# Boost_Kit.net
KiCad netlist of a schematic drawn in EAGLE
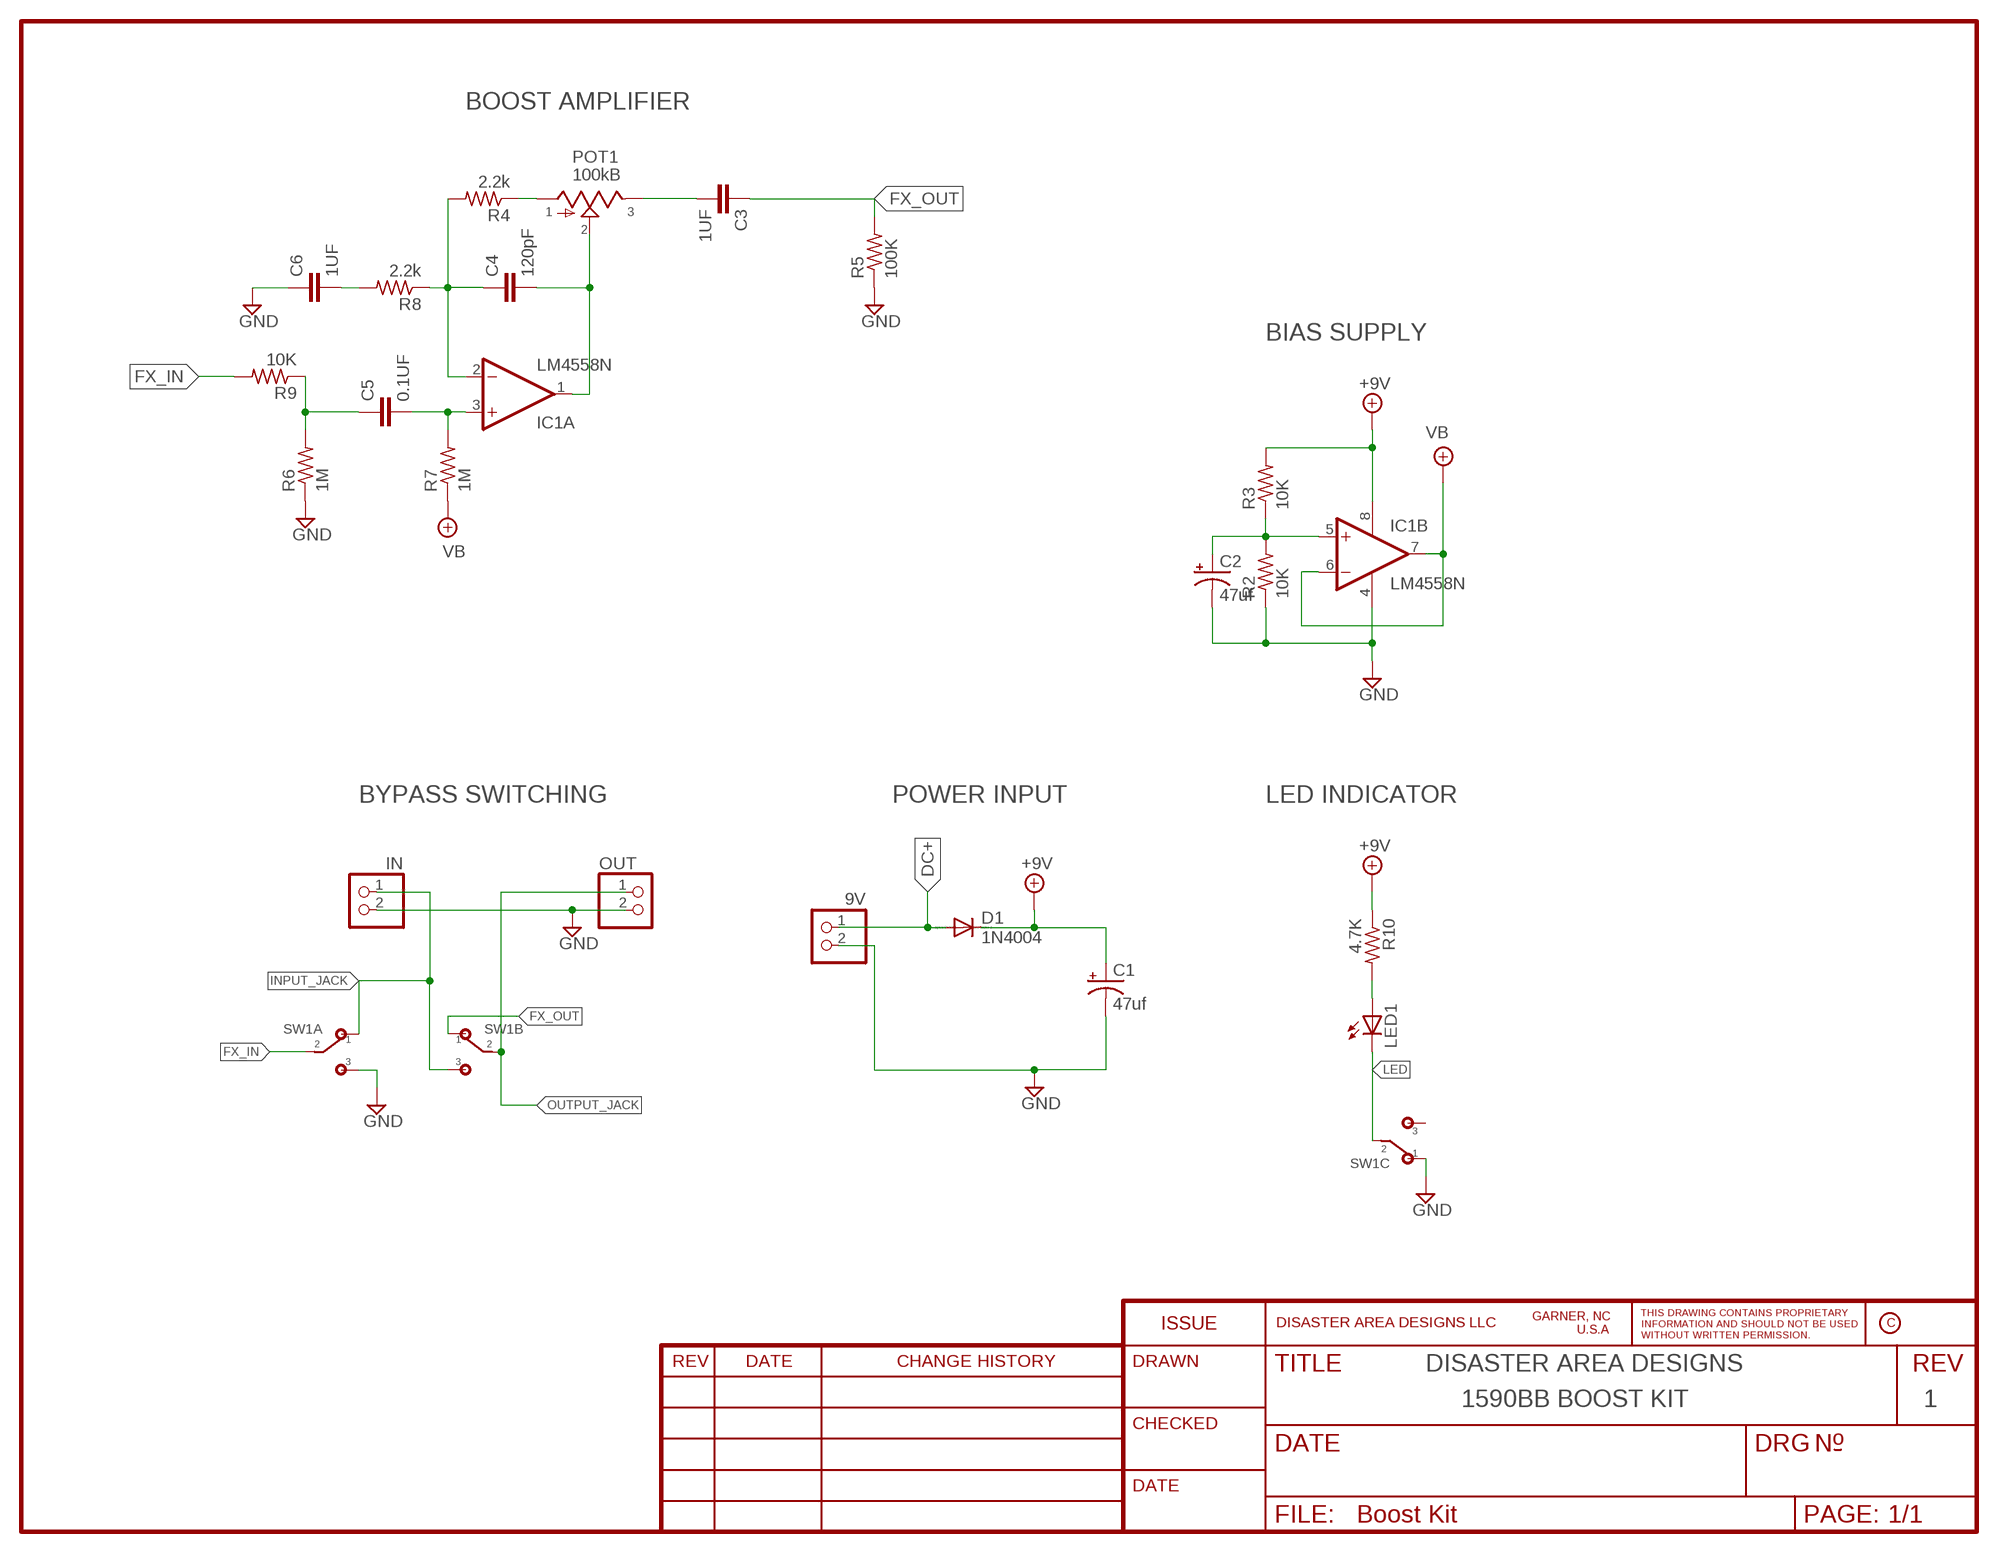
[diagram p0: schematic, sheet 1]

(export (version "E")
  (design (tool "Eeschema 10.0.6"))
  (components
    (comp (ref "9V")
      (value "PINHD-1X2")
      (footprint "eagle-import:1X02")
      (libsource (lib "eagle-import") (part "PINHD-1X2"))
    )
    (comp (ref "C1")
      (value "47uf")
      (footprint "eagle-import:E2,5-6")
      (libsource (lib "eagle-import") (part "CPOL-USE2.5-6"))
    )
    (comp (ref "C2")
      (value "47uf")
      (footprint "eagle-import:E2,5-6")
      (libsource (lib "eagle-import") (part "CPOL-USE2.5-6"))
    )
    (comp (ref "C3")
      (value "1UF")
      (footprint "eagle-import:072X035")
      (libsource (lib "eagle-import") (part "072X0352"))
    )
    (comp (ref "C4")
      (value "120pF")
      (footprint "eagle-import:072X035")
      (libsource (lib "eagle-import") (part "072X0352"))
    )
    (comp (ref "C5")
      (value "0.1UF")
      (footprint "eagle-import:072X035")
      (libsource (lib "eagle-import") (part "072X0352"))
    )
    (comp (ref "C6")
      (value "1UF")
      (footprint "eagle-import:072X035")
      (libsource (lib "eagle-import") (part "072X0352"))
    )
    (comp (ref "D1")
      (value "1N4004")
      (footprint "eagle-import:DO41-10")
      (libsource (lib "eagle-import") (part "1N4004"))
    )
    (comp (ref "IC1")
      (value "LM4558N")
      (footprint "eagle-import:DIL08")
      (libsource (lib "eagle-import") (part "4558NLM"))
    )
    (comp (ref "IN")
      (value "PINHD-1X2")
      (footprint "eagle-import:1X02")
      (libsource (lib "eagle-import") (part "PINHD-1X2"))
    )
    (comp (ref "LED1")
      (value "LED5MM")
      (footprint "eagle-import:LED5MM")
      (libsource (lib "eagle-import") (part "LED5MM"))
    )
    (comp (ref "OUT")
      (value "PINHD-1X2")
      (footprint "eagle-import:1X02")
      (libsource (lib "eagle-import") (part "PINHD-1X2"))
    )
    (comp (ref "POT1")
      (value "100kB")
      (footprint "eagle-import:16MM")
      (libsource (lib "eagle-import") (part "POT16MM"))
    )
    (comp (ref "R2")
      (value "10K")
      (footprint "eagle-import:R0207_4")
      (libsource (lib "eagle-import") (part "6MM.4"))
    )
    (comp (ref "R3")
      (value "10K")
      (footprint "eagle-import:R0207_4")
      (libsource (lib "eagle-import") (part "6MM.4"))
    )
    (comp (ref "R4")
      (value "2.2k")
      (footprint "eagle-import:R0207_4")
      (libsource (lib "eagle-import") (part "6MM.4"))
    )
    (comp (ref "R5")
      (value "100K")
      (footprint "eagle-import:R0207_4")
      (libsource (lib "eagle-import") (part "6MM.4"))
    )
    (comp (ref "R6")
      (value "1M")
      (footprint "eagle-import:R0207_4")
      (libsource (lib "eagle-import") (part "6MM.4"))
    )
    (comp (ref "R7")
      (value "1M")
      (footprint "eagle-import:R0207_4")
      (libsource (lib "eagle-import") (part "6MM.4"))
    )
    (comp (ref "R8")
      (value "2.2k")
      (footprint "eagle-import:R0207_4")
      (libsource (lib "eagle-import") (part "6MM.4"))
    )
    (comp (ref "R9")
      (value "10K")
      (footprint "eagle-import:R0207_4")
      (libsource (lib "eagle-import") (part "6MM.4"))
    )
    (comp (ref "R10")
      (value "4.7K")
      (footprint "eagle-import:R0207_4")
      (libsource (lib "eagle-import") (part "6MM.4"))
    )
    (comp (ref "SW1")
      (value "3PDT")
      (footprint "eagle-import:3PDT")
      (libsource (lib "eagle-import") (part "3PDT"))
    )
  )
  (nets
    (net (code "1") (name "+9V") (class "Default")
      (node (ref "C1") (pin "+") (pinfunction "+_+") (pintype "passive"))
      (node (ref "D1") (pin "C") (pinfunction "C_C") (pintype "passive"))
      (node (ref "IC1") (pin "8") (pinfunction "V+_8") (pintype "power_in"))
      (node (ref "R10") (pin "1") (pinfunction "1_1") (pintype "passive"))
      (node (ref "R3") (pin "2") (pinfunction "2_2") (pintype "passive"))
    )
    (net (code "2") (name "DC+") (class "Default")
      (node (ref "9V") (pin "1") (pinfunction "1_1") (pintype "passive"))
      (node (ref "D1") (pin "A") (pinfunction "A_A") (pintype "passive"))
    )
    (net (code "3") (name "FX_IN") (class "Default")
      (node (ref "R9") (pin "2") (pinfunction "2_2") (pintype "passive"))
      (node (ref "SW1") (pin "A2") (pinfunction "P$2_A2") (pintype "bidirectional"))
    )
    (net (code "4") (name "FX_OUT") (class "Default")
      (node (ref "C3") (pin "1") (pinfunction "1_1") (pintype "passive"))
      (node (ref "R5") (pin "2") (pinfunction "2_2") (pintype "passive"))
      (node (ref "SW1") (pin "B1") (pinfunction "P$1_B1") (pintype "bidirectional"))
    )
    (net (code "5") (name "GND") (class "Default")
      (node (ref "9V") (pin "2") (pinfunction "2_2") (pintype "passive"))
      (node (ref "C1") (pin "-") (pinfunction "-_-") (pintype "passive"))
      (node (ref "C2") (pin "-") (pinfunction "-_-") (pintype "passive"))
      (node (ref "C6") (pin "1") (pinfunction "1_1") (pintype "passive"))
      (node (ref "IC1") (pin "4") (pinfunction "V-_4") (pintype "power_in"))
      (node (ref "IN") (pin "2") (pinfunction "2_2") (pintype "passive"))
      (node (ref "OUT") (pin "2") (pinfunction "2_2") (pintype "passive"))
      (node (ref "R2") (pin "1") (pinfunction "1_1") (pintype "passive"))
      (node (ref "R5") (pin "1") (pinfunction "1_1") (pintype "passive"))
      (node (ref "R6") (pin "1") (pinfunction "1_1") (pintype "passive"))
      (node (ref "SW1") (pin "A3") (pinfunction "P$3_A3") (pintype "bidirectional"))
      (node (ref "SW1") (pin "C1") (pinfunction "P$1_C1") (pintype "bidirectional"))
    )
    (net (code "6") (name "INPUT_JACK") (class "Default")
      (node (ref "IN") (pin "1") (pinfunction "1_1") (pintype "passive"))
      (node (ref "SW1") (pin "A1") (pinfunction "P$1_A1") (pintype "bidirectional"))
      (node (ref "SW1") (pin "B3") (pinfunction "P$3_B3") (pintype "bidirectional"))
    )
    (net (code "7") (name "LED") (class "Default")
      (node (ref "LED1") (pin "K") (pinfunction "C_K") (pintype "passive"))
      (node (ref "SW1") (pin "C2") (pinfunction "P$2_C2") (pintype "bidirectional"))
    )
    (net (code "8") (name "Net-(C3-Pad2)") (class "Default")
      (node (ref "C3") (pin "2") (pinfunction "2_2") (pintype "passive"))
      (node (ref "POT1") (pin "3") (pinfunction "3_3") (pintype "passive"))
    )
    (net (code "9") (name "Net-(C5-Pad1)") (class "Default")
      (node (ref "C5") (pin "1") (pinfunction "1_1") (pintype "passive"))
      (node (ref "R6") (pin "2") (pinfunction "2_2") (pintype "passive"))
      (node (ref "R9") (pin "1") (pinfunction "1_1") (pintype "passive"))
    )
    (net (code "10") (name "Net-(C6-Pad2)") (class "Default")
      (node (ref "C6") (pin "2") (pinfunction "2_2") (pintype "passive"))
      (node (ref "R8") (pin "2") (pinfunction "2_2") (pintype "passive"))
    )
    (net (code "11") (name "Net-(IC1A-+IN)") (class "Default")
      (node (ref "C5") (pin "2") (pinfunction "2_2") (pintype "passive"))
      (node (ref "IC1") (pin "3") (pinfunction "+IN_3") (pintype "input"))
      (node (ref "R7") (pin "2") (pinfunction "2_2") (pintype "passive"))
    )
    (net (code "12") (name "Net-(IC1A--IN)") (class "Default")
      (node (ref "C4") (pin "1") (pinfunction "1_1") (pintype "passive"))
      (node (ref "IC1") (pin "2") (pinfunction "-IN_2") (pintype "input"))
      (node (ref "R4") (pin "2") (pinfunction "2_2") (pintype "passive"))
      (node (ref "R8") (pin "1") (pinfunction "1_1") (pintype "passive"))
    )
    (net (code "13") (name "Net-(IC1A-OUT)") (class "Default")
      (node (ref "C4") (pin "2") (pinfunction "2_2") (pintype "passive"))
      (node (ref "IC1") (pin "1") (pinfunction "OUT_1") (pintype "output"))
      (node (ref "POT1") (pin "2") (pinfunction "2_2") (pintype "passive"))
    )
    (net (code "14") (name "Net-(IC1B-+IN)") (class "Default")
      (node (ref "C2") (pin "+") (pinfunction "+_+") (pintype "passive"))
      (node (ref "IC1") (pin "5") (pinfunction "+IN_5") (pintype "input"))
      (node (ref "R2") (pin "2") (pinfunction "2_2") (pintype "passive"))
      (node (ref "R3") (pin "1") (pinfunction "1_1") (pintype "passive"))
    )
    (net (code "15") (name "Net-(LED1-PadA)") (class "Default")
      (node (ref "LED1") (pin "A") (pinfunction "A_A") (pintype "passive"))
      (node (ref "R10") (pin "2") (pinfunction "2_2") (pintype "passive"))
    )
    (net (code "16") (name "Net-(POT1-Pad1)") (class "Default")
      (node (ref "POT1") (pin "1") (pinfunction "1_1") (pintype "passive"))
      (node (ref "R4") (pin "1") (pinfunction "1_1") (pintype "passive"))
    )
    (net (code "17") (name "OUTPUT_JACK") (class "Default")
      (node (ref "OUT") (pin "1") (pinfunction "1_1") (pintype "passive"))
      (node (ref "SW1") (pin "B2") (pinfunction "P$2_B2") (pintype "bidirectional"))
    )
    (net (code "18") (name "VB") (class "Default")
      (node (ref "IC1") (pin "6") (pinfunction "-IN_6") (pintype "input"))
      (node (ref "IC1") (pin "7") (pinfunction "OUT_7") (pintype "output"))
      (node (ref "R7") (pin "1") (pinfunction "1_1") (pintype "passive"))
    )
    (net (code "19") (name "unconnected-(SW1C-P$3-PadC3)") (class "Default")
      (node (ref "SW1") (pin "C3") (pinfunction "P$3_C3") (pintype "bidirectional"))
    )
  )
)
